# Secondary_protection.net
KiCad netlist of a schematic drawn in Altium Designer
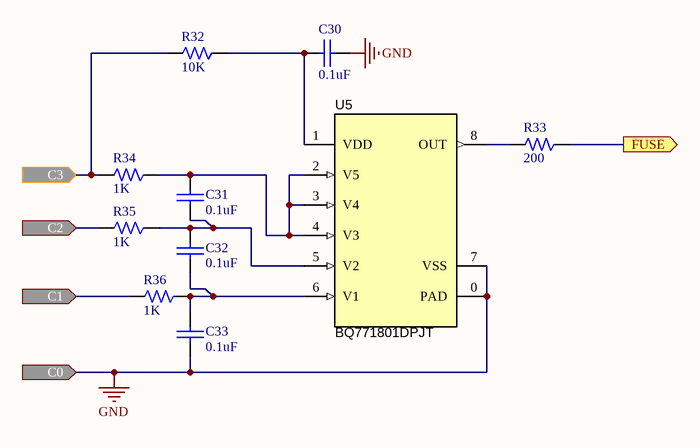
[diagram p0: Secondary protection.SchDoc]

(export (version "E")
  (design (tool "Eeschema 10.0.6"))
  (components
    (comp (ref "C30")
      (value "0.1uF")
      (footprint "CAPC0603-RW")
      (description "CAP X7R .01UF 16V +-10% 0603 WALSIN L")
      (fields
        (field (name "MFG") "WALSIN")
        (field (name "TOLERANCE") "10%")
        (field (name "CREATE_NAME") "Nathan")
      )
      (libsource (lib "P-Capacitors") (part "CAP0603 0.01uF 16V 10%_X7R_WALSIN"))
    )
    (comp (ref "C31")
      (value "0.1uF")
      (footprint "CAPC0603-RW")
      (description "CAP X7R .01UF 16V +-10% 0603 WALSIN L")
      (fields
        (field (name "MFG") "WALSIN")
        (field (name "TOLERANCE") "10%")
        (field (name "CREATE_NAME") "Nathan")
      )
      (libsource (lib "P-Capacitors") (part "CAP0603 0.01uF 16V 10%_X7R_WALSIN"))
    )
    (comp (ref "C32")
      (value "0.1uF")
      (footprint "CAPC0603-RW")
      (description "CAP X7R .01UF 16V +-10% 0603 WALSIN L")
      (fields
        (field (name "MFG") "WALSIN")
        (field (name "TOLERANCE") "10%")
        (field (name "CREATE_NAME") "Nathan")
      )
      (libsource (lib "P-Capacitors") (part "CAP0603 0.01uF 16V 10%_X7R_WALSIN"))
    )
    (comp (ref "C33")
      (value "0.1uF")
      (footprint "CAPC0603-RW")
      (description "CAP X7R .01UF 16V +-10% 0603 WALSIN L")
      (fields
        (field (name "MFG") "WALSIN")
        (field (name "TOLERANCE") "10%")
        (field (name "CREATE_NAME") "Nathan")
      )
      (libsource (lib "P-Capacitors") (part "CAP0603 0.01uF 16V 10%_X7R_WALSIN"))
    )
    (comp (ref "R32")
      (value "10K")
      (footprint "0603-RW")
      (description "CHIP 976 OHM 100PPM +-1% 0603 WALS L")
      (fields (field (name "POWER") "0.1W") (field (name "MFG") "WALSIN") (field (name "CREATE_NAME") "Tom"))
      (libsource (lib "Q-Resistors") (part "RES0603 1/10W +-1% 976 OHM 100PPM"))
    )
    (comp (ref "R33")
      (value "200")
      (footprint "0603-RW")
      (description "CHIP 976 OHM 100PPM +-1% 0603 WALS L")
      (fields (field (name "POWER") "0.1W") (field (name "MFG") "WALSIN") (field (name "CREATE_NAME") "Tom"))
      (libsource (lib "Q-Resistors") (part "RES0603 1/10W +-1% 976 OHM 100PPM"))
    )
    (comp (ref "R34")
      (value "1K")
      (footprint "0603-RW")
      (description "CHIP 976 OHM 100PPM +-1% 0603 WALS L")
      (fields (field (name "POWER") "0.1W") (field (name "MFG") "WALSIN") (field (name "CREATE_NAME") "Tom"))
      (libsource (lib "Q-Resistors") (part "RES0603 1/10W +-1% 976 OHM 100PPM"))
    )
    (comp (ref "R35")
      (value "1K")
      (footprint "0603-RW")
      (description "CHIP 976 OHM 100PPM +-1% 0603 WALS L")
      (fields (field (name "POWER") "0.1W") (field (name "MFG") "WALSIN") (field (name "CREATE_NAME") "Tom"))
      (libsource (lib "Q-Resistors") (part "RES0603 1/10W +-1% 976 OHM 100PPM"))
    )
    (comp (ref "R36")
      (value "1K")
      (footprint "0603-RW")
      (description "CHIP 976 OHM 100PPM +-1% 0603 WALS L")
      (fields (field (name "POWER") "0.1W") (field (name "MFG") "WALSIN") (field (name "CREATE_NAME") "Tom"))
      (libsource (lib "Q-Resistors") (part "RES0603 1/10W +-1% 976 OHM 100PPM"))
    )
    (comp (ref "U5")
      (value "BQ771801DPJT")
      (footprint "WSON(6x5x0.8)")
      (description "Family 2-5S Overvoltage Protector with Internal Delay Timer, DPJ0008A (WSON-8)")
      (fields
        (field (name "ALTERNATE PARTNUMBER") "BQ771801DPJR")
        (field (name "MANUFACTURER") "Texas Instruments")
        (field (name "PARTNUMBER") "BQ771801DPJT")
      )
      (libsource (lib "R-Semiconductors") (part "CMP-0078897-2"))
    )
  )
  (nets
    (net (code "1") (name "/C1") (class "Default")
      (node (ref "R36") (pin "2") (pinfunction "2_2") (pintype "passive"))
    )
    (net (code "2") (name "/C2") (class "Default")
      (node (ref "R35") (pin "2") (pinfunction "2_2") (pintype "passive"))
    )
    (net (code "3") (name "/C3") (class "Default")
      (node (ref "R32") (pin "2") (pinfunction "2_2") (pintype "passive"))
      (node (ref "R34") (pin "2") (pinfunction "2_2") (pintype "passive"))
    )
    (net (code "4") (name "/FUSE") (class "Default")
      (node (ref "R33") (pin "1") (pinfunction "1_1") (pintype "passive"))
    )
    (net (code "5") (name "GND") (class "Default")
      (node (ref "C30") (pin "2") (pinfunction "2_2") (pintype "passive"))
      (node (ref "C33") (pin "2") (pinfunction "2_2") (pintype "passive"))
      (node (ref "U5") (pin "0") (pinfunction "PAD_0") (pintype "passive"))
      (node (ref "U5") (pin "7") (pinfunction "VSS_7") (pintype "power_in"))
    )
    (net (code "6") (name "Net-(U5-OUT)") (class "Default")
      (node (ref "R33") (pin "2") (pinfunction "2_2") (pintype "passive"))
      (node (ref "U5") (pin "8") (pinfunction "OUT_8") (pintype "output"))
    )
    (net (code "7") (name "Net-(U5-V1)") (class "Default")
      (node (ref "C32") (pin "2") (pinfunction "2_2") (pintype "passive"))
      (node (ref "C33") (pin "1") (pinfunction "1_1") (pintype "passive"))
      (node (ref "R36") (pin "1") (pinfunction "1_1") (pintype "passive"))
      (node (ref "U5") (pin "6") (pinfunction "V1_6") (pintype "input"))
    )
    (net (code "8") (name "Net-(U5-V2)") (class "Default")
      (node (ref "C31") (pin "2") (pinfunction "2_2") (pintype "passive"))
      (node (ref "C32") (pin "1") (pinfunction "1_1") (pintype "passive"))
      (node (ref "R35") (pin "1") (pinfunction "1_1") (pintype "passive"))
      (node (ref "U5") (pin "5") (pinfunction "V2_5") (pintype "input"))
    )
    (net (code "9") (name "Net-(U5-V3)") (class "Default")
      (node (ref "C31") (pin "1") (pinfunction "1_1") (pintype "passive"))
      (node (ref "R34") (pin "1") (pinfunction "1_1") (pintype "passive"))
      (node (ref "U5") (pin "2") (pinfunction "V5_2") (pintype "input"))
      (node (ref "U5") (pin "3") (pinfunction "V4_3") (pintype "input"))
      (node (ref "U5") (pin "4") (pinfunction "V3_4") (pintype "input"))
    )
    (net (code "10") (name "Net-(U5-VDD)") (class "Default")
      (node (ref "C30") (pin "1") (pinfunction "1_1") (pintype "passive"))
      (node (ref "R32") (pin "1") (pinfunction "1_1") (pintype "passive"))
      (node (ref "U5") (pin "1") (pinfunction "VDD_1") (pintype "power_in"))
    )
  )
)
